# C_Axis_Endstop.net
KiCad netlist of a schematic drawn in EAGLE
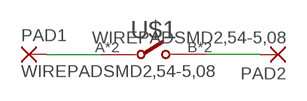
[diagram p0: schematic, sheet 1]

(export (version "E")
  (design (tool "Eeschema 10.0.6"))
  (components
    (comp (ref "PAD1")
      (value "WIREPADSMD2,54-5,08")
      (footprint "eagle-import:SMD2,54-5,08")
      (libsource (lib "eagle-import") (part "WIREPADSMD2,54-5,08"))
    )
    (comp (ref "PAD2")
      (value "WIREPADSMD2,54-5,08")
      (footprint "eagle-import:SMD2,54-5,08")
      (libsource (lib "eagle-import") (part "WIREPADSMD2,54-5,08"))
    )
    (comp (ref "U$1")
      (value "SWITCH_LIMIT_HDP001L")
      (footprint "eagle-import:SWITCH_LIMIT_HDP001L")
      (libsource (lib "eagle-import") (part "SWITCH_LIMIT_HDP001L"))
    )
  )
  (nets
    (net (code "1") (name "Net-(PAD1-P)") (class "Default")
      (node (ref "PAD1") (pin "1") (pinfunction "P_1") (pintype "passive"))
      (node (ref "U$1") (pin "A") (pinfunction "1_A") (pintype "passive"))
      (node (ref "U$1") (pin "C") (pinfunction "1_C") (pintype "passive"))
    )
    (net (code "2") (name "Net-(PAD2-P)") (class "Default")
      (node (ref "PAD2") (pin "1") (pinfunction "P_1") (pintype "passive"))
      (node (ref "U$1") (pin "B") (pinfunction "2_B") (pintype "passive"))
      (node (ref "U$1") (pin "D") (pinfunction "2_D") (pintype "passive"))
    )
  )
)
